# Bee_Hive_Scale_Board_3.net
KiCad netlist of a schematic drawn in Altium Designer
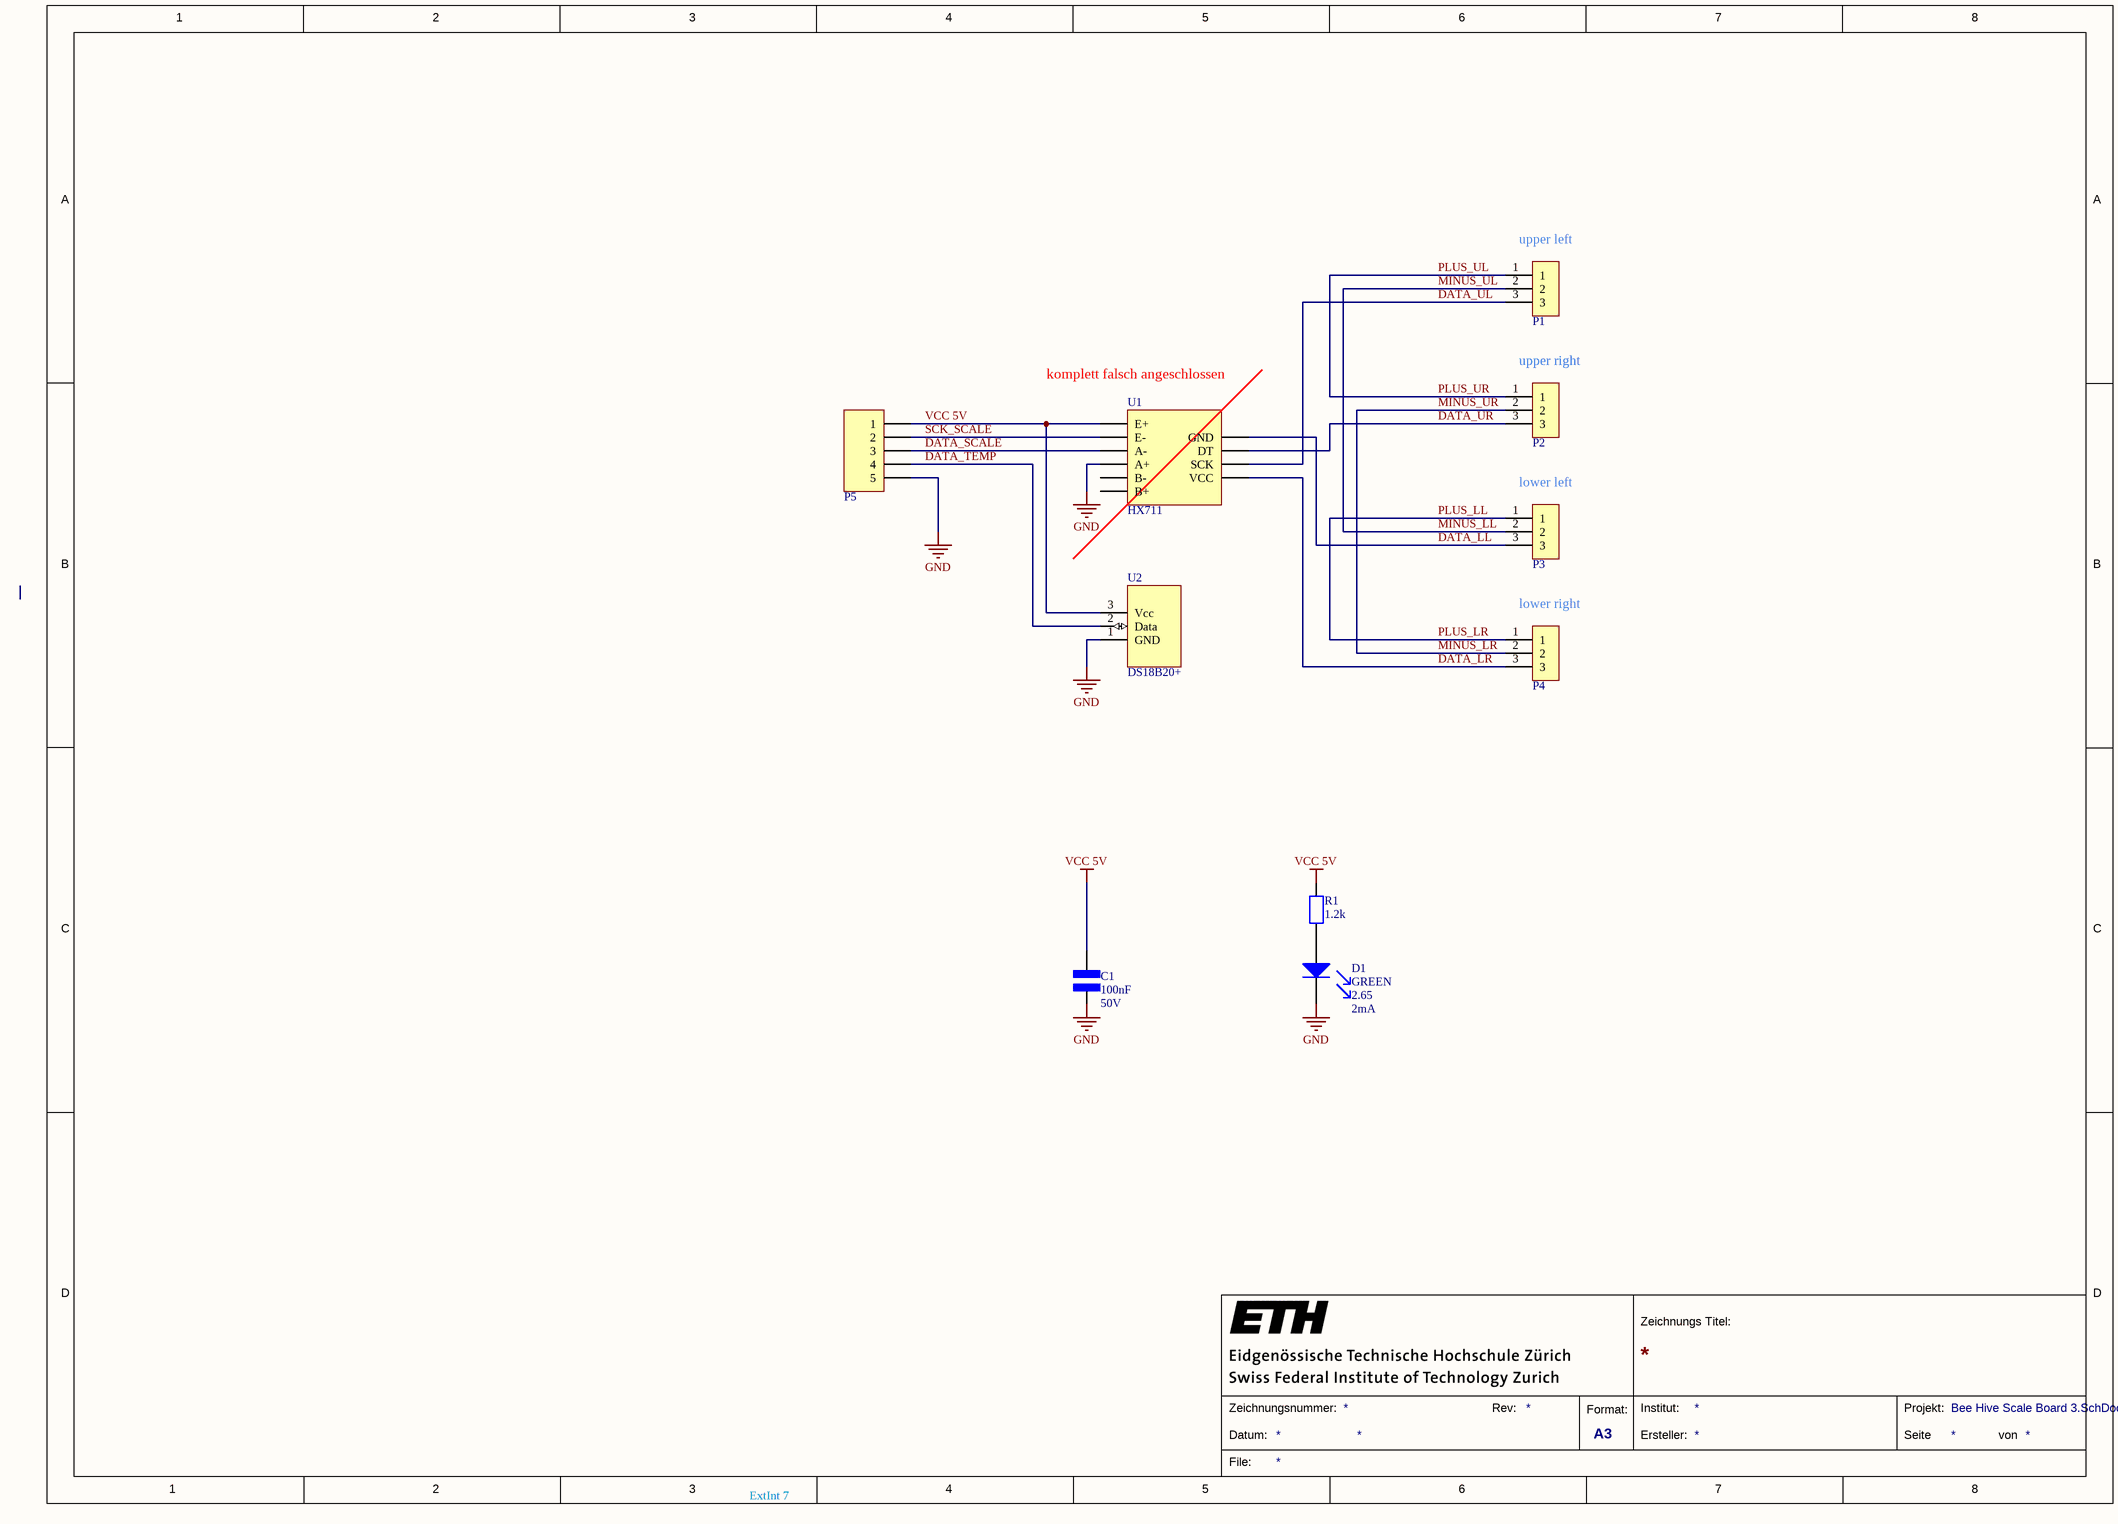
[diagram p0: Bee Hive Scale Board 3.SchDoc]

(export (version "E")
  (design (tool "Eeschema 10.0.6"))
  (components
    (comp (ref "C1")
      (value "100nF")
      (footprint "CAP 0603")
      (description "C CERAMIC SMD")
      (fields (field (name "UMAX") "50V") (field (name "Comment") "100nF 0603_1"))
      (libsource (lib "Library CAP") (part "100nF 0603_1"))
    )
    (comp (ref "D1")
      (value "LED Diode SMD LOW CURRENT")
      (footprint "LED SMD 0603 FOOTPRINT")
      (description "APT1608LZGCK")
      (fields
        (field (name "COLOR") "GREEN")
        (field (name "FORWARD VOLTAGE") "2.65")
        (field (name "IF") "2mA")
      )
      (libsource (lib "Library DIODE") (part "LED Diode SMD - GREEN - 0603 - 2mA_1"))
    )
    (comp (ref "P1")
      (value "3-Pin Right Angle Housing")
      (footprint "3PIN - Connector right angle")
      (description "3-Pin")
      (libsource (lib "Library Scematic") (part "3-Pin Right Angle"))
    )
    (comp (ref "P2")
      (value "3-Pin Right Angle Housing")
      (footprint "3PIN - Connector right angle")
      (description "3-Pin")
      (libsource (lib "Library Scematic") (part "3-Pin Right Angle"))
    )
    (comp (ref "P3")
      (value "3-Pin Right Angle Housing")
      (footprint "3PIN - Connector right angle")
      (description "3-Pin")
      (libsource (lib "Library Scematic") (part "3-Pin Right Angle"))
    )
    (comp (ref "P4")
      (value "3-Pin Right Angle Housing")
      (footprint "3PIN - Connector right angle")
      (description "3-Pin")
      (libsource (lib "Library Scematic") (part "3-Pin Right Angle"))
    )
    (comp (ref "P5")
      (value "comment")
      (footprint "5PIN")
      (description "5-Pin")
      (libsource (lib "Library Scematic") (part "5-Pin"))
    )
    (comp (ref "R1")
      (value "1.2k")
      (footprint "RES 0603 FOOTPRINT")
      (description "R SMD")
      (fields (field (name "Comment") "1.2k Ohm 0603"))
      (libsource (lib "Library RES") (part "1.2k Ohm 0603"))
    )
    (comp (ref "U1")
      (value "HX711")
      (footprint "HX711 SCALE - long")
      (description "HX711 XFW Alibaba Board")
      (libsource (lib "Library Scematic") (part "HX711 XFW Alibaba Board"))
    )
    (comp (ref "U2")
      (value "DS18B20+")
      (footprint "DS1820 Footprint")
      (description "Temperature Sensor, 12 Bit, OneWire, 3-pin TO-92")
      (libsource (lib "Library Scematic") (part "DS18B20"))
    )
  )
  (nets
    (net (code "1") (name "/DATA_LL") (class "Default")
      (node (ref "P3") (pin "3") (pinfunction "3_3") (pintype "passive"))
      (node (ref "U1") (pin "7") (pinfunction "GND_7") (pintype "passive"))
    )
    (net (code "2") (name "/DATA_LR") (class "Default")
      (node (ref "P4") (pin "3") (pinfunction "3_3") (pintype "passive"))
      (node (ref "U1") (pin "10") (pinfunction "VCC_10") (pintype "passive"))
    )
    (net (code "3") (name "/DATA_SCALE") (class "Default")
      (node (ref "P5") (pin "3") (pinfunction "3_3") (pintype "passive"))
      (node (ref "U1") (pin "3") (pinfunction "A-_3") (pintype "passive"))
    )
    (net (code "4") (name "/DATA_TEMP") (class "Default")
      (node (ref "P5") (pin "4") (pinfunction "4_4") (pintype "passive"))
      (node (ref "U2") (pin "2") (pinfunction "Data_2") (pintype "bidirectional"))
    )
    (net (code "5") (name "/DATA_UL") (class "Default")
      (node (ref "P1") (pin "3") (pinfunction "3_3") (pintype "passive"))
      (node (ref "U1") (pin "9") (pinfunction "SCK_9") (pintype "passive"))
    )
    (net (code "6") (name "/DATA_UR") (class "Default")
      (node (ref "P2") (pin "3") (pinfunction "3_3") (pintype "passive"))
      (node (ref "U1") (pin "8") (pinfunction "DT_8") (pintype "passive"))
    )
    (net (code "7") (name "/MINUS_LL") (class "Default")
      (node (ref "P1") (pin "2") (pinfunction "2_2") (pintype "passive"))
      (node (ref "P3") (pin "2") (pinfunction "2_2") (pintype "passive"))
    )
    (net (code "8") (name "/MINUS_LR") (class "Default")
      (node (ref "P2") (pin "2") (pinfunction "2_2") (pintype "passive"))
      (node (ref "P4") (pin "2") (pinfunction "2_2") (pintype "passive"))
    )
    (net (code "9") (name "/PLUS_LL") (class "Default")
      (node (ref "P3") (pin "1") (pinfunction "1_1") (pintype "passive"))
      (node (ref "P4") (pin "1") (pinfunction "1_1") (pintype "passive"))
    )
    (net (code "10") (name "/PLUS_UL") (class "Default")
      (node (ref "P1") (pin "1") (pinfunction "1_1") (pintype "passive"))
      (node (ref "P2") (pin "1") (pinfunction "1_1") (pintype "passive"))
    )
    (net (code "11") (name "/SCK_SCALE") (class "Default")
      (node (ref "P5") (pin "2") (pinfunction "2_2") (pintype "passive"))
      (node (ref "U1") (pin "2") (pinfunction "E-_2") (pintype "passive"))
    )
    (net (code "12") (name "GND") (class "Default")
      (node (ref "C1") (pin "1") (pinfunction "1_1") (pintype "passive"))
      (node (ref "D1") (pin "2") (pinfunction "K_2") (pintype "passive"))
      (node (ref "P5") (pin "5") (pinfunction "5_5") (pintype "passive"))
      (node (ref "U1") (pin "4") (pinfunction "A+_4") (pintype "passive"))
      (node (ref "U2") (pin "1") (pinfunction "GND_1") (pintype "power_in"))
    )
    (net (code "13") (name "Net-(D1-A)") (class "Default")
      (node (ref "D1") (pin "1") (pinfunction "A_1") (pintype "passive"))
      (node (ref "R1") (pin "1") (pinfunction "1_1") (pintype "passive"))
    )
    (net (code "14") (name "VCC 5V") (class "Default")
      (node (ref "C1") (pin "2") (pinfunction "2_2") (pintype "passive"))
      (node (ref "P5") (pin "1") (pinfunction "1_1") (pintype "passive"))
      (node (ref "R1") (pin "2") (pinfunction "2_2") (pintype "passive"))
      (node (ref "U1") (pin "1") (pinfunction "E+_1") (pintype "passive"))
      (node (ref "U2") (pin "3") (pinfunction "Vcc_3") (pintype "power_in"))
    )
    (net (code "15") (name "unconnected-(U1-B+-Pad6)") (class "Default")
      (node (ref "U1") (pin "6") (pinfunction "B+_6") (pintype "passive"))
    )
    (net (code "16") (name "unconnected-(U1-B--Pad5)") (class "Default")
      (node (ref "U1") (pin "5") (pinfunction "B-_5") (pintype "passive"))
    )
  )
)
